# IOT.net
KiCad netlist of a schematic drawn in EAGLE
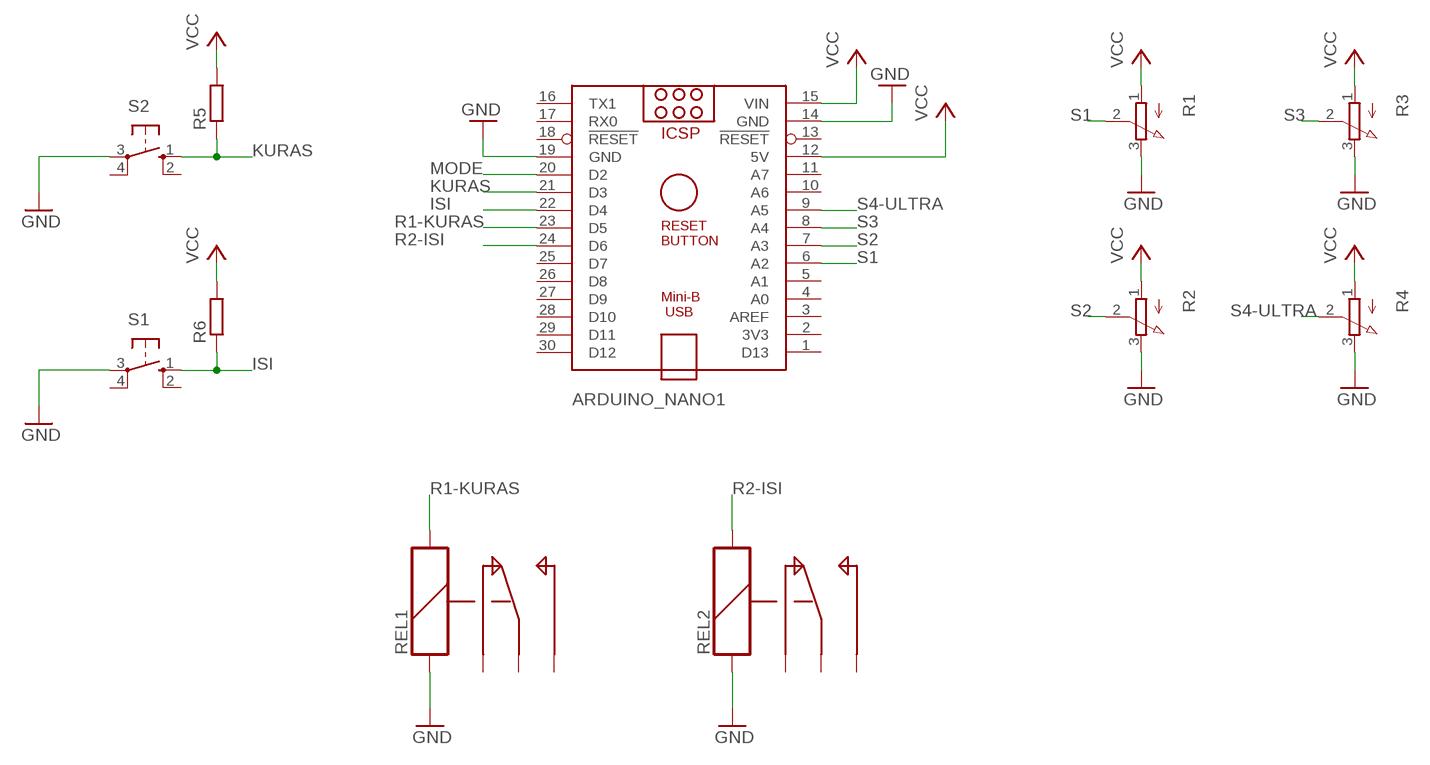
[diagram p0: schematic, sheet 1]

(export (version "E")
  (design (tool "Eeschema 10.0.6"))
  (components
    (comp (ref "ARDUINO_NANO1")
      (value "ARDUINO_NANO")
      (footprint "eagle-import:ARDUINO_NANO")
      (libsource (lib "eagle-import") (part "ARDUINO_NANO"))
    )
    (comp (ref "R1")
      (value "3RP/1610N")
      (footprint "eagle-import:3RP_1610N")
      (libsource (lib "eagle-import") (part "3RP/1610N"))
    )
    (comp (ref "R2")
      (value "3RP/1610N")
      (footprint "eagle-import:3RP_1610N")
      (libsource (lib "eagle-import") (part "3RP/1610N"))
    )
    (comp (ref "R3")
      (value "3RP/1610N")
      (footprint "eagle-import:3RP_1610N")
      (libsource (lib "eagle-import") (part "3RP/1610N"))
    )
    (comp (ref "R4")
      (value "3RP/1610N")
      (footprint "eagle-import:3RP_1610N")
      (libsource (lib "eagle-import") (part "3RP/1610N"))
    )
    (comp (ref "R5")
      (value "R-EU_0204/7")
      (footprint "eagle-import:0204_7")
      (libsource (lib "eagle-import") (part "R-EU_0204/7"))
    )
    (comp (ref "R6")
      (value "R-EU_0204/7")
      (footprint "eagle-import:0204_7")
      (libsource (lib "eagle-import") (part "R-EU_0204/7"))
    )
    (comp (ref "REL1")
      (value "REL-5PIN")
      (footprint "eagle-import:REL-5PIN")
      (libsource (lib "eagle-import") (part "REL-5PIN"))
    )
    (comp (ref "REL2")
      (value "REL-5PIN")
      (footprint "eagle-import:REL-5PIN")
      (libsource (lib "eagle-import") (part "REL-5PIN"))
    )
    (comp (ref "S1")
      (value "10-XX")
      (footprint "eagle-import:B3F-10XX")
      (fields (field (name "MPN") "B3F-1000"))
      (libsource (lib "eagle-import") (part "10-XX"))
    )
    (comp (ref "S2")
      (value "10-XX")
      (footprint "eagle-import:B3F-10XX")
      (fields (field (name "MPN") "B3F-1000"))
      (libsource (lib "eagle-import") (part "10-XX"))
    )
  )
  (nets
    (net (code "1") (name "/ISI") (class "Default")
      (node (ref "ARDUINO_NANO1") (pin "22") (pinfunction "D4_22") (pintype "bidirectional"))
      (node (ref "R6") (pin "1") (pinfunction "1_1") (pintype "passive"))
      (node (ref "S1") (pin "1") (pinfunction "S_1") (pintype "passive"))
    )
    (net (code "2") (name "/KURAS") (class "Default")
      (node (ref "ARDUINO_NANO1") (pin "21") (pinfunction "D3_21") (pintype "bidirectional"))
      (node (ref "R5") (pin "1") (pinfunction "1_1") (pintype "passive"))
      (node (ref "S2") (pin "1") (pinfunction "S_1") (pintype "passive"))
    )
    (net (code "3") (name "/MODE") (class "Default")
      (node (ref "ARDUINO_NANO1") (pin "20") (pinfunction "D2_20") (pintype "bidirectional"))
    )
    (net (code "4") (name "/R1-KURAS") (class "Default")
      (node (ref "ARDUINO_NANO1") (pin "23") (pinfunction "D5_23") (pintype "bidirectional"))
      (node (ref "REL1") (pin "S2") (pinfunction "S2_S2") (pintype "passive"))
    )
    (net (code "5") (name "/R2-ISI") (class "Default")
      (node (ref "ARDUINO_NANO1") (pin "24") (pinfunction "D6_24") (pintype "bidirectional"))
      (node (ref "REL2") (pin "S2") (pinfunction "S2_S2") (pintype "passive"))
    )
    (net (code "6") (name "/S1") (class "Default")
      (node (ref "ARDUINO_NANO1") (pin "6") (pinfunction "A2_6") (pintype "bidirectional"))
      (node (ref "R1") (pin "2") (pinfunction "S_2") (pintype "passive"))
    )
    (net (code "7") (name "/S2") (class "Default")
      (node (ref "ARDUINO_NANO1") (pin "7") (pinfunction "A3_7") (pintype "bidirectional"))
      (node (ref "R2") (pin "2") (pinfunction "S_2") (pintype "passive"))
    )
    (net (code "8") (name "/S3") (class "Default")
      (node (ref "ARDUINO_NANO1") (pin "8") (pinfunction "A4_8") (pintype "bidirectional"))
      (node (ref "R3") (pin "2") (pinfunction "S_2") (pintype "passive"))
    )
    (net (code "9") (name "/S4-ULTRA") (class "Default")
      (node (ref "ARDUINO_NANO1") (pin "9") (pinfunction "A5_9") (pintype "bidirectional"))
      (node (ref "R4") (pin "2") (pinfunction "S_2") (pintype "passive"))
    )
    (net (code "10") (name "GND") (class "Default")
      (node (ref "ARDUINO_NANO1") (pin "14") (pinfunction "GND_14") (pintype "power_in"))
      (node (ref "ARDUINO_NANO1") (pin "19") (pinfunction "GND_19") (pintype "power_in"))
      (node (ref "R1") (pin "3") (pinfunction "E_3") (pintype "passive"))
      (node (ref "R2") (pin "3") (pinfunction "E_3") (pintype "passive"))
      (node (ref "R3") (pin "3") (pinfunction "E_3") (pintype "passive"))
      (node (ref "R4") (pin "3") (pinfunction "E_3") (pintype "passive"))
      (node (ref "REL1") (pin "S1") (pinfunction "S1_S1") (pintype "passive"))
      (node (ref "REL2") (pin "S1") (pinfunction "S1_S1") (pintype "passive"))
      (node (ref "S1") (pin "3") (pinfunction "P_3") (pintype "passive"))
      (node (ref "S2") (pin "3") (pinfunction "P_3") (pintype "passive"))
    )
    (net (code "11") (name "VCC") (class "Default")
      (node (ref "ARDUINO_NANO1") (pin "12") (pinfunction "5V_12") (pintype "power_in"))
      (node (ref "ARDUINO_NANO1") (pin "15") (pinfunction "VIN_15") (pintype "power_in"))
      (node (ref "R1") (pin "1") (pinfunction "A_1") (pintype "passive"))
      (node (ref "R2") (pin "1") (pinfunction "A_1") (pintype "passive"))
      (node (ref "R3") (pin "1") (pinfunction "A_1") (pintype "passive"))
      (node (ref "R4") (pin "1") (pinfunction "A_1") (pintype "passive"))
      (node (ref "R5") (pin "2") (pinfunction "2_2") (pintype "passive"))
      (node (ref "R6") (pin "2") (pinfunction "2_2") (pintype "passive"))
    )
    (net (code "12") (name "unconnected-(ARDUINO_NANO1-3V3-Pad2)") (class "Default")
      (node (ref "ARDUINO_NANO1") (pin "2") (pinfunction "3V3_2") (pintype "output"))
    )
    (net (code "13") (name "unconnected-(ARDUINO_NANO1-A0-Pad4)") (class "Default")
      (node (ref "ARDUINO_NANO1") (pin "4") (pinfunction "A0_4") (pintype "bidirectional"))
    )
    (net (code "14") (name "unconnected-(ARDUINO_NANO1-A1-Pad5)") (class "Default")
      (node (ref "ARDUINO_NANO1") (pin "5") (pinfunction "A1_5") (pintype "bidirectional"))
    )
    (net (code "15") (name "unconnected-(ARDUINO_NANO1-A6-Pad10)") (class "Default")
      (node (ref "ARDUINO_NANO1") (pin "10") (pinfunction "A6_10") (pintype "bidirectional"))
    )
    (net (code "16") (name "unconnected-(ARDUINO_NANO1-A7-Pad11)") (class "Default")
      (node (ref "ARDUINO_NANO1") (pin "11") (pinfunction "A7_11") (pintype "bidirectional"))
    )
    (net (code "17") (name "unconnected-(ARDUINO_NANO1-AREF-Pad3)") (class "Default")
      (node (ref "ARDUINO_NANO1") (pin "3") (pinfunction "AREF_3") (pintype "input"))
    )
    (net (code "18") (name "unconnected-(ARDUINO_NANO1-D7-Pad25)") (class "Default")
      (node (ref "ARDUINO_NANO1") (pin "25") (pinfunction "D7_25") (pintype "bidirectional"))
    )
    (net (code "19") (name "unconnected-(ARDUINO_NANO1-D8-Pad26)") (class "Default")
      (node (ref "ARDUINO_NANO1") (pin "26") (pinfunction "D8_26") (pintype "bidirectional"))
    )
    (net (code "20") (name "unconnected-(ARDUINO_NANO1-D9-Pad27)") (class "Default")
      (node (ref "ARDUINO_NANO1") (pin "27") (pinfunction "D9_27") (pintype "bidirectional"))
    )
    (net (code "21") (name "unconnected-(ARDUINO_NANO1-D10-Pad28)") (class "Default")
      (node (ref "ARDUINO_NANO1") (pin "28") (pinfunction "D10_28") (pintype "bidirectional"))
    )
    (net (code "22") (name "unconnected-(ARDUINO_NANO1-D11-Pad29)") (class "Default")
      (node (ref "ARDUINO_NANO1") (pin "29") (pinfunction "D11_29") (pintype "bidirectional"))
    )
    (net (code "23") (name "unconnected-(ARDUINO_NANO1-D12-Pad30)") (class "Default")
      (node (ref "ARDUINO_NANO1") (pin "30") (pinfunction "D12_30") (pintype "bidirectional"))
    )
    (net (code "24") (name "unconnected-(ARDUINO_NANO1-D13-Pad1)") (class "Default")
      (node (ref "ARDUINO_NANO1") (pin "1") (pinfunction "D13_1") (pintype "bidirectional"))
    )
    (net (code "25") (name "unconnected-(ARDUINO_NANO1-RX0-Pad17)") (class "Default")
      (node (ref "ARDUINO_NANO1") (pin "17") (pinfunction "RX0_17") (pintype "bidirectional"))
    )
    (net (code "26") (name "unconnected-(ARDUINO_NANO1-TX1-Pad16)") (class "Default")
      (node (ref "ARDUINO_NANO1") (pin "16") (pinfunction "TX1_16") (pintype "bidirectional"))
    )
    (net (code "27") (name "unconnected-(ARDUINO_NANO1-~{RESET}-Pad13)") (class "Default")
      (node (ref "ARDUINO_NANO1") (pin "13") (pinfunction "~{RESET}_13") (pintype "input"))
    )
    (net (code "28") (name "unconnected-(ARDUINO_NANO1-~{RESET}-Pad18)") (class "Default")
      (node (ref "ARDUINO_NANO1") (pin "18") (pinfunction "~{RESET}_18") (pintype "input"))
    )
    (net (code "29") (name "unconnected-(REL1-PadC)") (class "Default")
      (node (ref "REL1") (pin "C") (pinfunction "C_C") (pintype "passive"))
    )
    (net (code "30") (name "unconnected-(REL1-PadO)") (class "Default")
      (node (ref "REL1") (pin "O") (pinfunction "O_O") (pintype "passive"))
    )
    (net (code "31") (name "unconnected-(REL1-PadS)") (class "Default")
      (node (ref "REL1") (pin "S") (pinfunction "S_S") (pintype "passive"))
    )
    (net (code "32") (name "unconnected-(REL2-PadC)") (class "Default")
      (node (ref "REL2") (pin "C") (pinfunction "C_C") (pintype "passive"))
    )
    (net (code "33") (name "unconnected-(REL2-PadO)") (class "Default")
      (node (ref "REL2") (pin "O") (pinfunction "O_O") (pintype "passive"))
    )
    (net (code "34") (name "unconnected-(REL2-PadS)") (class "Default")
      (node (ref "REL2") (pin "S") (pinfunction "S_S") (pintype "passive"))
    )
    (net (code "35") (name "unconnected-(S1-P1-Pad4)") (class "Default")
      (node (ref "S1") (pin "4") (pinfunction "P1_4") (pintype "passive"))
    )
    (net (code "36") (name "unconnected-(S1-S1-Pad2)") (class "Default")
      (node (ref "S1") (pin "2") (pinfunction "S1_2") (pintype "passive"))
    )
    (net (code "37") (name "unconnected-(S2-P1-Pad4)") (class "Default")
      (node (ref "S2") (pin "4") (pinfunction "P1_4") (pintype "passive"))
    )
    (net (code "38") (name "unconnected-(S2-S1-Pad2)") (class "Default")
      (node (ref "S2") (pin "2") (pinfunction "S1_2") (pintype "passive"))
    )
  )
)
